# GPS.net
KiCad netlist of a schematic drawn in Altium Designer
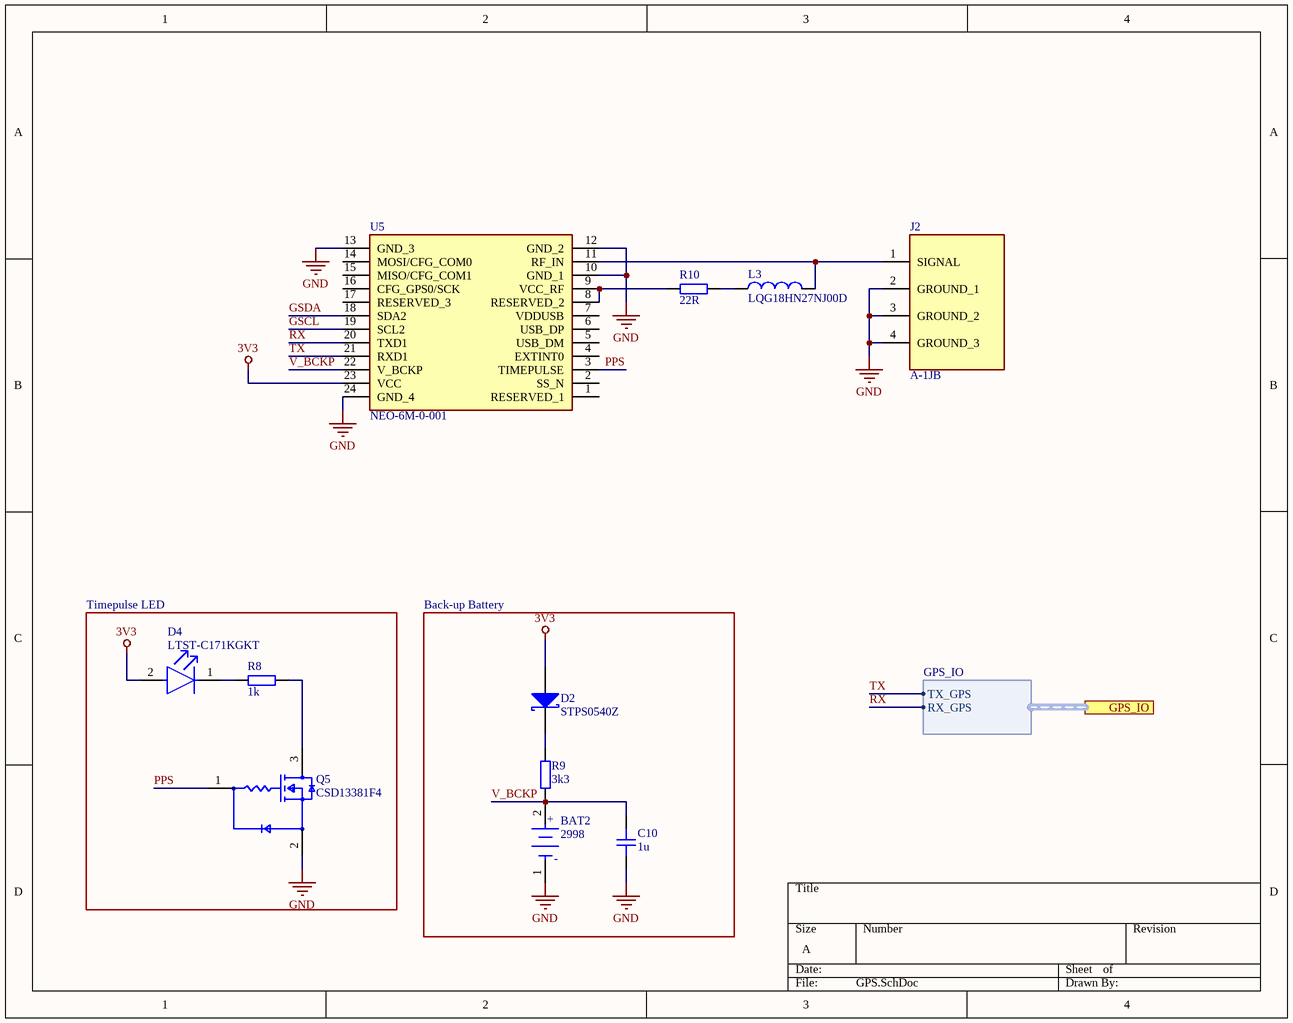
[diagram p0: GPS.SchDoc]

(export (version "E")
  (design (tool "Eeschema 10.0.6"))
  (components
    (comp (ref "BAT2")
      (value "2998")
      (footprint "BAT_2998TR")
      (description "BATTERY RETAINER COIN 6.8MM SMD")
      (libsource (lib "Schlib1") (part "2998"))
    )
    (comp (ref "C10")
      (value "1u")
      (footprint "CAP_0603")
      (description "Ceramic Capacitor SMD 0603")
      (libsource (lib "Schlib1") (part "CAP_0603"))
    )
    (comp (ref "D2")
      (value "STPS0540Z")
      (footprint "STM-SOD-123-2_V")
      (description "Schottky Rectifier, 0.5 A, 40 V, 2-Pin SOP (SOD-123), RoHS, Tape and Reel")
      (fields (field (name "MANUFACTURER") "STMicroelectronics"))
      (libsource (lib "Altium Content Vault") (part "DSKY-AK-2"))
    )
    (comp (ref "D4")
      (value "LTST-C171KGKT")
      (footprint "FP-LTST-C171KGKT-MFG")
      (description "LED GREEN CLEAR SMD")
      (libsource (lib "Altium Content Vault") (part "8706943c75ba83719d021d2fdc84c58"))
    )
    (comp (ref "J2")
      (value "A-1JB")
      (footprint "A1JB")
      (description "U.FL (UMCC), AMC Connector Jack, Male Pin 50 Ohms Surface Mount Solder")
      (fields (field (name "MOUSER PART NUMBER") "523-A-1JB"))
      (libsource (lib "Schlib1") (part "A-1JB"))
    )
    (comp (ref "L3")
      (value "LQG18HN27NJ00D")
      (footprint "PcbLib1:CAP_0603")
      (description "Ind RF Chip Multi-Layer 27nH 5% 100MHz 12Q-Factor Air 300mA 0603 Paper T/R")
      (libsource (lib "Schlib1") (part "LQG18HN27NJ00D"))
    )
    (comp (ref "Q5")
      (value "CSD13381F4")
      (footprint "FP-CSD13381F4-MFG")
      (description "MOSFET N-CH 12V 2.1A 3PICOSTAR")
      (libsource (lib "Altium Content Vault") (part "9fa42dd10ff43da9cbcc9b3293ff909"))
    )
    (comp (ref "R8")
      (value "1k")
      (footprint "RES_0603")
      (description "Resistor SMD 0603")
      (libsource (lib "Generic library") (part "RES_0603"))
    )
    (comp (ref "R9")
      (value "3k3")
      (footprint "RES_0603")
      (description "Resistor SMD 0603")
      (libsource (lib "Generic library") (part "RES_0603"))
    )
    (comp (ref "R10")
      (value "22R")
      (footprint "RES_0603")
      (description "Resistor SMD 0603")
      (libsource (lib "Generic library") (part "RES_0603"))
    )
    (comp (ref "U5")
      (value "NEO-6M-0-001")
      (footprint "NEO6M0001")
      (description "GPS Module")
      (libsource (lib "Schlib1") (part "NEO-6M-0-001"))
    )
  )
  (nets
    (net (code "2") (name "/GSCL") (class "Default")
      (node (ref "U5") (pin "19") (pinfunction "SCL2_19") (pintype "passive"))
    )
    (net (code "3") (name "/GSDA") (class "Default")
      (node (ref "U5") (pin "18") (pinfunction "SDA2_18") (pintype "passive"))
    )
    (net (code "4") (name "/PPS") (class "Default")
      (node (ref "Q5") (pin "1") (pinfunction "G_1") (pintype "passive"))
      (node (ref "U5") (pin "3") (pinfunction "TIMEPULSE_3") (pintype "passive"))
    )
    (net (code "5") (name "/RX") (class "Default")
      (node (ref "U5") (pin "20") (pinfunction "TXD1_20") (pintype "passive"))
    )
    (net (code "6") (name "/TX") (class "Default")
      (node (ref "U5") (pin "21") (pinfunction "RXD1_21") (pintype "passive"))
    )
    (net (code "7") (name "/V_BCKP") (class "Default")
      (node (ref "BAT2") (pin "2") (pinfunction "A_2") (pintype "passive"))
      (node (ref "C10") (pin "2") (pinfunction "2_2") (pintype "passive"))
      (node (ref "R9") (pin "1") (pinfunction "1_1") (pintype "passive"))
      (node (ref "U5") (pin "22") (pinfunction "V_BCKP_22") (pintype "passive"))
    )
    (net (code "9") (name "3V3") (class "Default")
      (node (ref "D2") (pin "1") (pinfunction "A_1") (pintype "passive"))
      (node (ref "D4") (pin "2") (pinfunction "A_2") (pintype "passive"))
      (node (ref "U5") (pin "23") (pinfunction "VCC_23") (pintype "passive"))
    )
    (net (code "10") (name "GND") (class "Default")
      (node (ref "BAT2") (pin "1") (pinfunction "C_1") (pintype "passive"))
      (node (ref "C10") (pin "1") (pinfunction "1_1") (pintype "passive"))
      (node (ref "J2") (pin "2") (pinfunction "GROUND_1_2") (pintype "passive"))
      (node (ref "J2") (pin "3") (pinfunction "GROUND_2_3") (pintype "passive"))
      (node (ref "J2") (pin "4") (pinfunction "GROUND_3_4") (pintype "passive"))
      (node (ref "Q5") (pin "2") (pinfunction "S_2") (pintype "passive"))
      (node (ref "U5") (pin "10") (pinfunction "GND_1_10") (pintype "passive"))
      (node (ref "U5") (pin "12") (pinfunction "GND_2_12") (pintype "passive"))
      (node (ref "U5") (pin "13") (pinfunction "GND_3_13") (pintype "passive"))
      (node (ref "U5") (pin "24") (pinfunction "GND_4_24") (pintype "passive"))
    )
    (net (code "11") (name "Net-(D2-K)") (class "Default")
      (node (ref "D2") (pin "2") (pinfunction "K_2") (pintype "passive"))
      (node (ref "R9") (pin "2") (pinfunction "2_2") (pintype "passive"))
    )
    (net (code "12") (name "Net-(D4-C)") (class "Default")
      (node (ref "D4") (pin "1") (pinfunction "C_1") (pintype "passive"))
      (node (ref "R8") (pin "1") (pinfunction "1_1") (pintype "passive"))
    )
    (net (code "13") (name "Net-(J2-SIGNAL)") (class "Default")
      (node (ref "J2") (pin "1") (pinfunction "SIGNAL_1") (pintype "passive"))
      (node (ref "L3") (pin "2") (pinfunction "2_2") (pintype "passive"))
      (node (ref "U5") (pin "11") (pinfunction "RF_IN_11") (pintype "passive"))
    )
    (net (code "14") (name "Net-(L3-Pad1)") (class "Default")
      (node (ref "L3") (pin "1") (pinfunction "1_1") (pintype "passive"))
      (node (ref "R10") (pin "2") (pinfunction "2_2") (pintype "passive"))
    )
    (net (code "15") (name "Net-(Q5-D)") (class "Default")
      (node (ref "Q5") (pin "3") (pinfunction "D_3") (pintype "passive"))
      (node (ref "R8") (pin "2") (pinfunction "2_2") (pintype "passive"))
    )
    (net (code "16") (name "Net-(U5-RESERVED_2)") (class "Default")
      (node (ref "R10") (pin "1") (pinfunction "1_1") (pintype "passive"))
      (node (ref "U5") (pin "8") (pinfunction "RESERVED_2_8") (pintype "passive"))
      (node (ref "U5") (pin "9") (pinfunction "VCC_RF_9") (pintype "passive"))
    )
    (net (code "17") (name "unconnected-(U5-CFG_GPS0{slash}SCK-Pad16)") (class "Default")
      (node (ref "U5") (pin "16") (pinfunction "CFG_GPS0/SCK_16") (pintype "passive"))
    )
    (net (code "18") (name "unconnected-(U5-EXTINT0-Pad4)") (class "Default")
      (node (ref "U5") (pin "4") (pinfunction "EXTINT0_4") (pintype "passive"))
    )
    (net (code "19") (name "unconnected-(U5-MISO{slash}CFG_COM1-Pad15)") (class "Default")
      (node (ref "U5") (pin "15") (pinfunction "MISO/CFG_COM1_15") (pintype "passive"))
    )
    (net (code "20") (name "unconnected-(U5-MOSI{slash}CFG_COM0-Pad14)") (class "Default")
      (node (ref "U5") (pin "14") (pinfunction "MOSI/CFG_COM0_14") (pintype "passive"))
    )
    (net (code "21") (name "unconnected-(U5-RESERVED_1-Pad1)") (class "Default")
      (node (ref "U5") (pin "1") (pinfunction "RESERVED_1_1") (pintype "passive"))
    )
    (net (code "22") (name "unconnected-(U5-RESERVED_3-Pad17)") (class "Default")
      (node (ref "U5") (pin "17") (pinfunction "RESERVED_3_17") (pintype "passive"))
    )
    (net (code "23") (name "unconnected-(U5-SS_N-Pad2)") (class "Default")
      (node (ref "U5") (pin "2") (pinfunction "SS_N_2") (pintype "passive"))
    )
    (net (code "24") (name "unconnected-(U5-USB_DM-Pad5)") (class "Default")
      (node (ref "U5") (pin "5") (pinfunction "USB_DM_5") (pintype "passive"))
    )
    (net (code "25") (name "unconnected-(U5-USB_DP-Pad6)") (class "Default")
      (node (ref "U5") (pin "6") (pinfunction "USB_DP_6") (pintype "passive"))
    )
    (net (code "26") (name "unconnected-(U5-VDDUSB-Pad7)") (class "Default")
      (node (ref "U5") (pin "7") (pinfunction "VDDUSB_7") (pintype "passive"))
    )
  )
)
